# power_switch.net
KiCad netlist of a schematic drawn in EAGLE
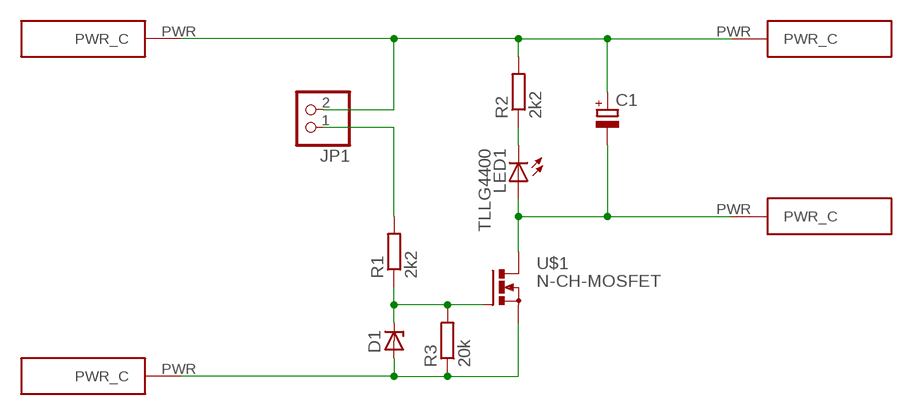
[diagram p0: schematic, sheet 1]

(export (version "E")
  (design (tool "Eeschema 10.0.6"))
  (components
    (comp (ref "C1")
      (value "CPOL-EUE7.5-16")
      (footprint "eagle-import:E7,5-16")
      (libsource (lib "eagle-import") (part "CPOL-EUE7.5-16"))
    )
    (comp (ref "D1")
      (value "ZENER-DIODEDO41Z10")
      (footprint "eagle-import:DO41Z10")
      (libsource (lib "eagle-import") (part "ZENER-DIODEDO41Z10"))
    )
    (comp (ref "JP1")
      (value "PINHD-1X2")
      (footprint "eagle-import:1X02")
      (libsource (lib "eagle-import") (part "PINHD-1X2"))
    )
    (comp (ref "LED1")
      (value "TLLG4400")
      (footprint "eagle-import:LED3MM")
      (fields (field (name "MF") "VISHAY SEMICONDUCTOR"))
      (libsource (lib "eagle-import") (part "TLLG4400"))
    )
    (comp (ref "R1")
      (value "2k2")
      (footprint "eagle-import:0204_7")
      (libsource (lib "eagle-import") (part "R-EU_0204/7"))
    )
    (comp (ref "R2")
      (value "2k2")
      (footprint "eagle-import:0204_7")
      (libsource (lib "eagle-import") (part "R-EU_0204/7"))
    )
    (comp (ref "R3")
      (value "20k")
      (footprint "eagle-import:0204_7")
      (libsource (lib "eagle-import") (part "R-EU_0204/7"))
    )
    (comp (ref "U$1")
      (value "N-CH-MOSFET")
      (footprint "eagle-import:TO220BV")
      (libsource (lib "eagle-import") (part "N-CH-MOSFET"))
    )
    (comp (ref "U$2")
      (value "24V")
      (footprint "eagle-import:SMD_PAD")
      (libsource (lib "eagle-import") (part "POWERCONNECTOR"))
    )
    (comp (ref "U$3")
      (value "POWERCONNECTOR")
      (footprint "eagle-import:SMD_PAD")
      (libsource (lib "eagle-import") (part "POWERCONNECTOR"))
    )
    (comp (ref "U$4")
      (value "POWERCONNECTOR")
      (footprint "eagle-import:SMD_PAD")
      (libsource (lib "eagle-import") (part "POWERCONNECTOR"))
    )
    (comp (ref "U$5")
      (value "POWERCONNECTOR")
      (footprint "eagle-import:SMD_PAD")
      (libsource (lib "eagle-import") (part "POWERCONNECTOR"))
    )
  )
  (nets
    (net (code "1") (name "Net-(D1-PadC)") (class "Default")
      (node (ref "D1") (pin "C") (pinfunction "C_C") (pintype "passive"))
      (node (ref "R1") (pin "1") (pinfunction "1_1") (pintype "passive"))
      (node (ref "R3") (pin "2") (pinfunction "2_2") (pintype "passive"))
      (node (ref "U$1") (pin "G") (pinfunction "G_G") (pintype "passive"))
    )
    (net (code "2") (name "Net-(JP1-Pad1)") (class "Default")
      (node (ref "JP1") (pin "1") (pinfunction "1_1") (pintype "passive"))
      (node (ref "R1") (pin "2") (pinfunction "2_2") (pintype "passive"))
    )
    (net (code "3") (name "Net-(LED1-C)") (class "Default")
      (node (ref "LED1") (pin "K") (pinfunction "C_K") (pintype "passive"))
      (node (ref "R2") (pin "1") (pinfunction "1_1") (pintype "passive"))
    )
    (net (code "4") (name "Net-(U$2-PWR_C)") (class "Default")
      (node (ref "C1") (pin "+") (pinfunction "+_+") (pintype "passive"))
      (node (ref "JP1") (pin "2") (pinfunction "2_2") (pintype "passive"))
      (node (ref "R2") (pin "2") (pinfunction "2_2") (pintype "passive"))
      (node (ref "U$2") (pin "PWR") (pinfunction "PWR_C_PWR") (pintype "bidirectional"))
      (node (ref "U$4") (pin "PWR") (pinfunction "PWR_C_PWR") (pintype "bidirectional"))
    )
    (net (code "5") (name "Net-(U$3-PWR_C)") (class "Default")
      (node (ref "D1") (pin "A") (pinfunction "A_A") (pintype "passive"))
      (node (ref "R3") (pin "1") (pinfunction "1_1") (pintype "passive"))
      (node (ref "U$1") (pin "S") (pinfunction "S_S") (pintype "passive"))
      (node (ref "U$3") (pin "PWR") (pinfunction "PWR_C_PWR") (pintype "bidirectional"))
    )
    (net (code "6") (name "Net-(U$5-PWR_C)") (class "Default")
      (node (ref "C1") (pin "-") (pinfunction "-_-") (pintype "passive"))
      (node (ref "LED1") (pin "A") (pinfunction "A_A") (pintype "passive"))
      (node (ref "U$1") (pin "D") (pinfunction "D_D") (pintype "passive"))
      (node (ref "U$5") (pin "PWR") (pinfunction "PWR_C_PWR") (pintype "bidirectional"))
    )
  )
)
